# SolarConnectors.net
KiCad netlist of a schematic drawn in Altium Designer
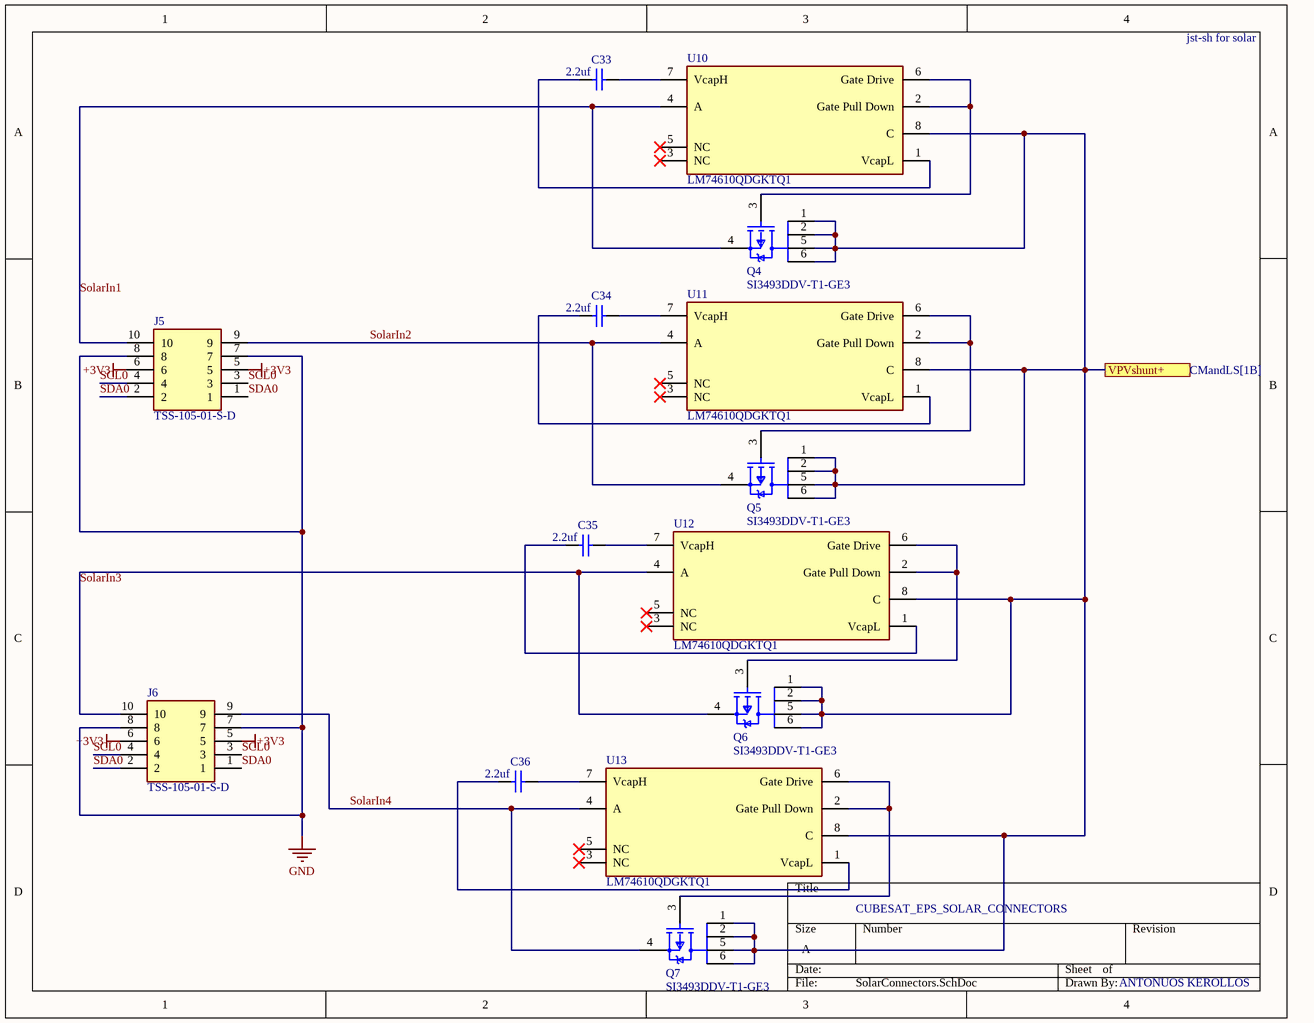
[diagram p0: SolarConnectors.SchDoc]

(export (version "E")
  (design (tool "Eeschema 10.0.6"))
  (components
    (comp (ref "C33")
      (value "2.2uf")
      (footprint "CAPC2013X145X50ML20T25")
      (fields (field (name "PART NUMBER") "C0805C225K9PACTU") (field (name "MANUFACTURER") "Kemet"))
      (libsource (lib "Altium Content Vault") (part "CAP"))
    )
    (comp (ref "C34")
      (value "2.2uf")
      (footprint "CAPC2013X145X50ML20T25")
      (fields (field (name "PART NUMBER") "C0805C225K9PACTU") (field (name "MANUFACTURER") "Kemet"))
      (libsource (lib "Altium Content Vault") (part "CAP"))
    )
    (comp (ref "C35")
      (value "2.2uf")
      (footprint "CAPC2013X145X50ML20T25")
      (fields (field (name "PART NUMBER") "C0805C225K9PACTU") (field (name "MANUFACTURER") "Kemet"))
      (libsource (lib "Altium Content Vault") (part "CAP"))
    )
    (comp (ref "C36")
      (value "2.2uf")
      (footprint "CAPC2013X145X50ML20T25")
      (fields (field (name "PART NUMBER") "C0805C225K9PACTU") (field (name "MANUFACTURER") "Kemet"))
      (libsource (lib "Altium Content Vault") (part "CAP"))
    )
    (comp (ref "J5")
      (value "TSS-105-01-S-D")
      (footprint "SamacSys:TSS-105-XX-YYY-D")
      (description "Connector")
      (fields (field (name "MOUSER PART NUMBER") "200-TSS10501SD"))
      (libsource (lib "*") (part "TSS-105-01-S-D"))
    )
    (comp (ref "J6")
      (value "TSS-105-01-S-D")
      (footprint "SamacSys:TSS-105-XX-YYY-D")
      (description "Connector")
      (fields (field (name "MOUSER PART NUMBER") "200-TSS10501SD"))
      (libsource (lib "*") (part "TSS-105-01-S-D"))
    )
    (comp (ref "Q4")
      (value "SI3493DDV-T1-GE3")
      (footprint "FP-C-06593-MFG")
      (description "MOSFET P-CHANNEL 20V 8A 6TSOP")
      (fields
        (field (name "MANUFACTURER") "Vishay")
        (field (name "OCTOPART") "https://octopart.com/si3493ddv-t1-ge3-vishay-81014282")
      )
      (libsource (lib "Altium Content Vault") (part "cb80e2443ef6eac25cf60ecf9c1abdf"))
    )
    (comp (ref "Q5")
      (value "SI3493DDV-T1-GE3")
      (footprint "FP-C-06593-MFG")
      (description "MOSFET P-CHANNEL 20V 8A 6TSOP")
      (fields
        (field (name "MANUFACTURER") "Vishay")
        (field (name "OCTOPART") "https://octopart.com/si3493ddv-t1-ge3-vishay-81014282")
      )
      (libsource (lib "Altium Content Vault") (part "cb80e2443ef6eac25cf60ecf9c1abdf"))
    )
    (comp (ref "Q6")
      (value "SI3493DDV-T1-GE3")
      (footprint "FP-C-06593-MFG")
      (description "MOSFET P-CHANNEL 20V 8A 6TSOP")
      (fields
        (field (name "MANUFACTURER") "Vishay")
        (field (name "OCTOPART") "https://octopart.com/si3493ddv-t1-ge3-vishay-81014282")
      )
      (libsource (lib "Altium Content Vault") (part "cb80e2443ef6eac25cf60ecf9c1abdf"))
    )
    (comp (ref "Q7")
      (value "SI3493DDV-T1-GE3")
      (footprint "FP-C-06593-MFG")
      (description "MOSFET P-CHANNEL 20V 8A 6TSOP")
      (fields
        (field (name "MANUFACTURER") "Vishay")
        (field (name "OCTOPART") "https://octopart.com/si3493ddv-t1-ge3-vishay-81014282")
      )
      (libsource (lib "Altium Content Vault") (part "cb80e2443ef6eac25cf60ecf9c1abdf"))
    )
    (comp (ref "U10")
      (value "LM74610QDGKTQ1")
      (footprint "FP-DGK0008A-MFG")
      (description "IC SMART DIODE CTLR 8VSSOP")
      (fields
        (field (name "MANUFACTURER") "Texas Instruments")
        (field (name "OCTOPART") "https://octopart.com/lm74610qdgktq1-texas+instruments-61765970")
      )
      (libsource (lib "Altium Content Vault") (part "c7658b1ea207364c60caa1c767b42c9"))
    )
    (comp (ref "U11")
      (value "LM74610QDGKTQ1")
      (footprint "FP-DGK0008A-MFG")
      (description "IC SMART DIODE CTLR 8VSSOP")
      (fields
        (field (name "MANUFACTURER") "Texas Instruments")
        (field (name "OCTOPART") "https://octopart.com/lm74610qdgktq1-texas+instruments-61765970")
      )
      (libsource (lib "Altium Content Vault") (part "c7658b1ea207364c60caa1c767b42c9"))
    )
    (comp (ref "U12")
      (value "LM74610QDGKTQ1")
      (footprint "FP-DGK0008A-MFG")
      (description "IC SMART DIODE CTLR 8VSSOP")
      (fields
        (field (name "MANUFACTURER") "Texas Instruments")
        (field (name "OCTOPART") "https://octopart.com/lm74610qdgktq1-texas+instruments-61765970")
      )
      (libsource (lib "Altium Content Vault") (part "c7658b1ea207364c60caa1c767b42c9"))
    )
    (comp (ref "U13")
      (value "LM74610QDGKTQ1")
      (footprint "FP-DGK0008A-MFG")
      (description "IC SMART DIODE CTLR 8VSSOP")
      (fields
        (field (name "MANUFACTURER") "Texas Instruments")
        (field (name "OCTOPART") "https://octopart.com/lm74610qdgktq1-texas+instruments-61765970")
      )
      (libsource (lib "Altium Content Vault") (part "c7658b1ea207364c60caa1c767b42c9"))
    )
  )
  (nets
    (net (code "1") (name "+3V3") (class "Default")
      (node (ref "J5") (pin "5") (pinfunction "5_5") (pintype "passive"))
      (node (ref "J5") (pin "6") (pinfunction "6_6") (pintype "passive"))
      (node (ref "J6") (pin "5") (pinfunction "5_5") (pintype "passive"))
      (node (ref "J6") (pin "6") (pinfunction "6_6") (pintype "passive"))
    )
    (net (code "2") (name "/SCL0") (class "Default")
      (node (ref "J5") (pin "3") (pinfunction "3_3") (pintype "passive"))
      (node (ref "J5") (pin "4") (pinfunction "4_4") (pintype "passive"))
      (node (ref "J6") (pin "3") (pinfunction "3_3") (pintype "passive"))
      (node (ref "J6") (pin "4") (pinfunction "4_4") (pintype "passive"))
    )
    (net (code "3") (name "/SDA0") (class "Default")
      (node (ref "J5") (pin "1") (pinfunction "1_1") (pintype "passive"))
      (node (ref "J5") (pin "2") (pinfunction "2_2") (pintype "passive"))
      (node (ref "J6") (pin "1") (pinfunction "1_1") (pintype "passive"))
      (node (ref "J6") (pin "2") (pinfunction "2_2") (pintype "passive"))
    )
    (net (code "4") (name "/SolarIn1") (class "Default")
      (node (ref "J5") (pin "10") (pinfunction "10_10") (pintype "passive"))
      (node (ref "Q4") (pin "4") (pinfunction "S_4") (pintype "passive"))
      (node (ref "U10") (pin "4") (pinfunction "A_4") (pintype "passive"))
    )
    (net (code "5") (name "/SolarIn2") (class "Default")
      (node (ref "J5") (pin "9") (pinfunction "9_9") (pintype "passive"))
      (node (ref "Q5") (pin "4") (pinfunction "S_4") (pintype "passive"))
      (node (ref "U11") (pin "4") (pinfunction "A_4") (pintype "passive"))
    )
    (net (code "6") (name "/SolarIn3") (class "Default")
      (node (ref "J6") (pin "10") (pinfunction "10_10") (pintype "passive"))
      (node (ref "Q6") (pin "4") (pinfunction "S_4") (pintype "passive"))
      (node (ref "U12") (pin "4") (pinfunction "A_4") (pintype "passive"))
    )
    (net (code "7") (name "/SolarIn4") (class "Default")
      (node (ref "J6") (pin "9") (pinfunction "9_9") (pintype "passive"))
      (node (ref "Q7") (pin "4") (pinfunction "S_4") (pintype "passive"))
      (node (ref "U13") (pin "4") (pinfunction "A_4") (pintype "passive"))
    )
    (net (code "8") (name "/VPVshunt+") (class "Default")
      (node (ref "Q4") (pin "1") (pinfunction "D_1") (pintype "passive"))
      (node (ref "Q4") (pin "2") (pinfunction "D_2") (pintype "passive"))
      (node (ref "Q4") (pin "5") (pinfunction "D_5") (pintype "passive"))
      (node (ref "Q4") (pin "6") (pinfunction "D_6") (pintype "passive"))
      (node (ref "Q5") (pin "1") (pinfunction "D_1") (pintype "passive"))
      (node (ref "Q5") (pin "2") (pinfunction "D_2") (pintype "passive"))
      (node (ref "Q5") (pin "5") (pinfunction "D_5") (pintype "passive"))
      (node (ref "Q5") (pin "6") (pinfunction "D_6") (pintype "passive"))
      (node (ref "Q6") (pin "1") (pinfunction "D_1") (pintype "passive"))
      (node (ref "Q6") (pin "2") (pinfunction "D_2") (pintype "passive"))
      (node (ref "Q6") (pin "5") (pinfunction "D_5") (pintype "passive"))
      (node (ref "Q6") (pin "6") (pinfunction "D_6") (pintype "passive"))
      (node (ref "Q7") (pin "1") (pinfunction "D_1") (pintype "passive"))
      (node (ref "Q7") (pin "2") (pinfunction "D_2") (pintype "passive"))
      (node (ref "Q7") (pin "5") (pinfunction "D_5") (pintype "passive"))
      (node (ref "Q7") (pin "6") (pinfunction "D_6") (pintype "passive"))
      (node (ref "U10") (pin "8") (pinfunction "C_8") (pintype "passive"))
      (node (ref "U11") (pin "8") (pinfunction "C_8") (pintype "passive"))
      (node (ref "U12") (pin "8") (pinfunction "C_8") (pintype "passive"))
      (node (ref "U13") (pin "8") (pinfunction "C_8") (pintype "passive"))
    )
    (net (code "9") (name "GND") (class "Default")
      (node (ref "J5") (pin "7") (pinfunction "7_7") (pintype "passive"))
      (node (ref "J5") (pin "8") (pinfunction "8_8") (pintype "passive"))
      (node (ref "J6") (pin "7") (pinfunction "7_7") (pintype "passive"))
      (node (ref "J6") (pin "8") (pinfunction "8_8") (pintype "passive"))
    )
    (net (code "10") (name "Net-(Q4-G)") (class "Default")
      (node (ref "Q4") (pin "3") (pinfunction "G_3") (pintype "passive"))
      (node (ref "U10") (pin "2") (pinfunction "Gate_Pull_Down_2") (pintype "passive"))
      (node (ref "U10") (pin "6") (pinfunction "Gate_Drive_6") (pintype "passive"))
    )
    (net (code "11") (name "Net-(Q5-G)") (class "Default")
      (node (ref "Q5") (pin "3") (pinfunction "G_3") (pintype "passive"))
      (node (ref "U11") (pin "2") (pinfunction "Gate_Pull_Down_2") (pintype "passive"))
      (node (ref "U11") (pin "6") (pinfunction "Gate_Drive_6") (pintype "passive"))
    )
    (net (code "12") (name "Net-(Q6-G)") (class "Default")
      (node (ref "Q6") (pin "3") (pinfunction "G_3") (pintype "passive"))
      (node (ref "U12") (pin "2") (pinfunction "Gate_Pull_Down_2") (pintype "passive"))
      (node (ref "U12") (pin "6") (pinfunction "Gate_Drive_6") (pintype "passive"))
    )
    (net (code "13") (name "Net-(Q7-G)") (class "Default")
      (node (ref "Q7") (pin "3") (pinfunction "G_3") (pintype "passive"))
      (node (ref "U13") (pin "2") (pinfunction "Gate_Pull_Down_2") (pintype "passive"))
      (node (ref "U13") (pin "6") (pinfunction "Gate_Drive_6") (pintype "passive"))
    )
    (net (code "14") (name "Net-(U10-VcapH)") (class "Default")
      (node (ref "C33") (pin "1") (pinfunction "1_1") (pintype "passive"))
      (node (ref "U10") (pin "7") (pinfunction "VcapH_7") (pintype "power_in"))
    )
    (net (code "15") (name "Net-(U10-VcapL)") (class "Default")
      (node (ref "C33") (pin "2") (pinfunction "2_2") (pintype "passive"))
      (node (ref "U10") (pin "1") (pinfunction "VcapL_1") (pintype "power_in"))
    )
    (net (code "16") (name "Net-(U11-VcapH)") (class "Default")
      (node (ref "C34") (pin "1") (pinfunction "1_1") (pintype "passive"))
      (node (ref "U11") (pin "7") (pinfunction "VcapH_7") (pintype "power_in"))
    )
    (net (code "17") (name "Net-(U11-VcapL)") (class "Default")
      (node (ref "C34") (pin "2") (pinfunction "2_2") (pintype "passive"))
      (node (ref "U11") (pin "1") (pinfunction "VcapL_1") (pintype "power_in"))
    )
    (net (code "18") (name "Net-(U12-VcapH)") (class "Default")
      (node (ref "C35") (pin "1") (pinfunction "1_1") (pintype "passive"))
      (node (ref "U12") (pin "7") (pinfunction "VcapH_7") (pintype "power_in"))
    )
    (net (code "19") (name "Net-(U12-VcapL)") (class "Default")
      (node (ref "C35") (pin "2") (pinfunction "2_2") (pintype "passive"))
      (node (ref "U12") (pin "1") (pinfunction "VcapL_1") (pintype "power_in"))
    )
    (net (code "20") (name "Net-(U13-VcapH)") (class "Default")
      (node (ref "C36") (pin "1") (pinfunction "1_1") (pintype "passive"))
      (node (ref "U13") (pin "7") (pinfunction "VcapH_7") (pintype "power_in"))
    )
    (net (code "21") (name "Net-(U13-VcapL)") (class "Default")
      (node (ref "C36") (pin "2") (pinfunction "2_2") (pintype "passive"))
      (node (ref "U13") (pin "1") (pinfunction "VcapL_1") (pintype "power_in"))
    )
    (net (code "22") (name "unconnected-(U10-NC-Pad3)") (class "Default")
      (node (ref "U10") (pin "3") (pinfunction "NC_3") (pintype "passive+no_connect"))
    )
    (net (code "23") (name "unconnected-(U10-NC-Pad5)") (class "Default")
      (node (ref "U10") (pin "5") (pinfunction "NC_5") (pintype "passive+no_connect"))
    )
    (net (code "24") (name "unconnected-(U11-NC-Pad3)") (class "Default")
      (node (ref "U11") (pin "3") (pinfunction "NC_3") (pintype "passive+no_connect"))
    )
    (net (code "25") (name "unconnected-(U11-NC-Pad5)") (class "Default")
      (node (ref "U11") (pin "5") (pinfunction "NC_5") (pintype "passive+no_connect"))
    )
    (net (code "26") (name "unconnected-(U12-NC-Pad3)") (class "Default")
      (node (ref "U12") (pin "3") (pinfunction "NC_3") (pintype "passive+no_connect"))
    )
    (net (code "27") (name "unconnected-(U12-NC-Pad5)") (class "Default")
      (node (ref "U12") (pin "5") (pinfunction "NC_5") (pintype "passive+no_connect"))
    )
    (net (code "28") (name "unconnected-(U13-NC-Pad3)") (class "Default")
      (node (ref "U13") (pin "3") (pinfunction "NC_3") (pintype "passive+no_connect"))
    )
    (net (code "29") (name "unconnected-(U13-NC-Pad5)") (class "Default")
      (node (ref "U13") (pin "5") (pinfunction "NC_5") (pintype "passive+no_connect"))
    )
  )
)
